# ICs.net
KiCad netlist of a schematic drawn in Altium Designer
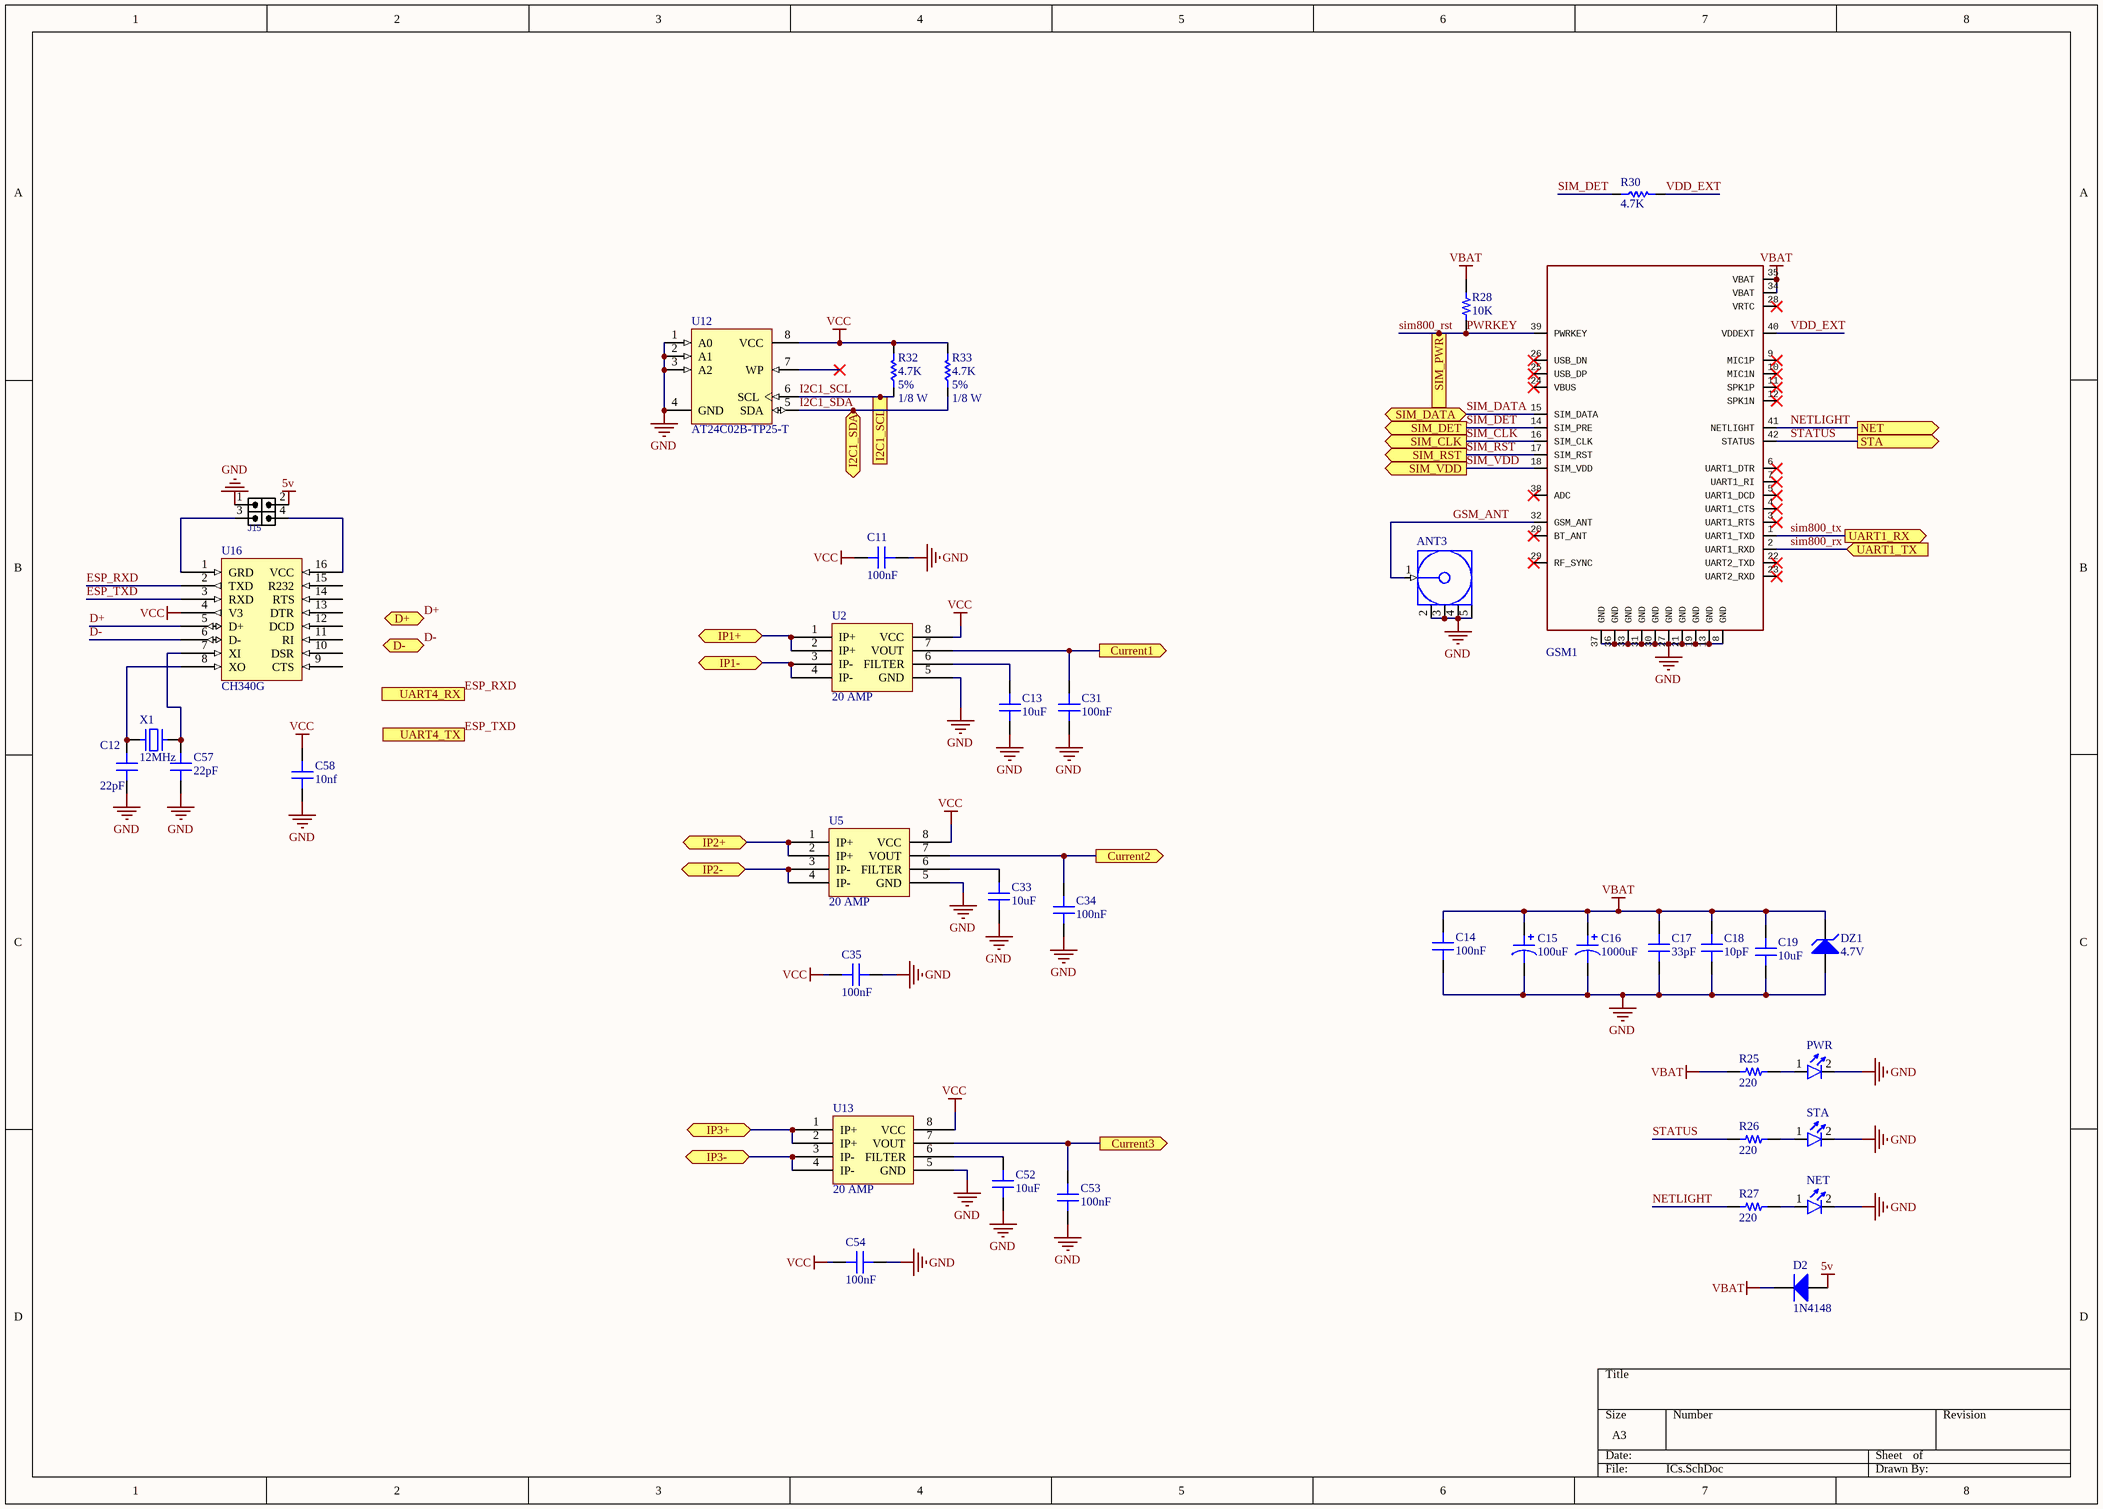
[diagram p0: ICs.SchDoc]

(export (version "E")
  (design (tool "Eeschema 10.0.6"))
  (components
    (comp (ref "ANT3") (value "SMA") (footprint "SMA_RA") (libsource (lib "CONNECTOR") (part "SMA RA")))
    (comp (ref "C11")
      (value "100nF")
      (footprint "CAP 0603_1608")
      (description "SMT Capacitor")
      (libsource (lib "CAPACITOR") (part "Cap SMD 0805"))
    )
    (comp (ref "C12")
      (value "22pF")
      (footprint "CAP 0805")
      (description "SMT Capacitor")
      (libsource (lib "CAPACITOR") (part "Cap SMD 0805"))
    )
    (comp (ref "C13")
      (value "10uF")
      (footprint "CAP 0805")
      (description "SMT Capacitor")
      (libsource (lib "CAPACITOR") (part "Cap SMD 0805"))
    )
    (comp (ref "C14")
      (value "100nF")
      (footprint "CAP 0805")
      (description "SMT Capacitor")
      (libsource (lib "CAPACITOR") (part "Cap SMD 0805"))
    )
    (comp (ref "C15")
      (value "100uF")
      (footprint "CAP TAN SMD 3528")
      (description "SMT TAN Polarised Capacitor")
      (libsource (lib "CAPACITOR") (part "Pol Cap SMD TAN 3528 SIZE B"))
    )
    (comp (ref "C16")
      (value "1000uF")
      (footprint "CAP ALSMD POLY 8.3MM H8.0MM")
      (description "SMT Polarised Capacitor")
      (libsource (lib "CAPACITOR") (part "Pol Cap SMD AL D4 H4"))
    )
    (comp (ref "C17")
      (value "33pF")
      (footprint "CAP 0805")
      (description "SMT Capacitor")
      (libsource (lib "CAPACITOR") (part "Cap SMD 0805"))
    )
    (comp (ref "C18")
      (value "10pF")
      (footprint "CAP 0805")
      (description "SMT Capacitor")
      (libsource (lib "CAPACITOR") (part "Cap SMD 0805"))
    )
    (comp (ref "C19")
      (value "10uF")
      (footprint "CAP 0805")
      (description "SMT Capacitor")
      (libsource (lib "CAPACITOR") (part "Cap SMD 0805"))
    )
    (comp (ref "C31")
      (value "100nF")
      (footprint "CAP 0603_1608")
      (description "SMT Capacitor")
      (libsource (lib "CAPACITOR") (part "Cap SMD 0805"))
    )
    (comp (ref "C33")
      (value "10uF")
      (footprint "CAP 0805")
      (description "SMT Capacitor")
      (libsource (lib "CAPACITOR") (part "Cap SMD 0805"))
    )
    (comp (ref "C34")
      (value "100nF")
      (footprint "CAP 0603_1608")
      (description "SMT Capacitor")
      (libsource (lib "CAPACITOR") (part "Cap SMD 0805"))
    )
    (comp (ref "C35")
      (value "100nF")
      (footprint "CAP 0603_1608")
      (description "SMT Capacitor")
      (libsource (lib "CAPACITOR") (part "Cap SMD 0805"))
    )
    (comp (ref "C52")
      (value "10uF")
      (footprint "CAP 0805_2012")
      (description "SMT Capacitor")
      (libsource (lib "CAPACITOR") (part "Cap SMD 0805"))
    )
    (comp (ref "C53")
      (value "100nF")
      (footprint "CAP 0603_1608")
      (description "SMT Capacitor")
      (libsource (lib "CAPACITOR") (part "Cap SMD 0805"))
    )
    (comp (ref "C54")
      (value "100nF")
      (footprint "CAP 0603_1608")
      (description "SMT Capacitor")
      (libsource (lib "CAPACITOR") (part "Cap SMD 0805"))
    )
    (comp (ref "C57")
      (value "22pF")
      (footprint "CAP 0805")
      (description "SMT Capacitor")
      (libsource (lib "CAPACITOR") (part "Cap SMD 0805"))
    )
    (comp (ref "C58")
      (value "10nf")
      (footprint "CAP 0805")
      (description "SMT Capacitor")
      (libsource (lib "CAPACITOR") (part "Cap SMD 0805"))
    )
    (comp (ref "D2")
      (value "1N4148 SMD")
      (footprint "DO-214AA SMB")
      (description "Signal Diode")
      (fields (field (name "PARAMETER 1") "1N4148"))
      (libsource (lib "DIODE") (part "1N4148 SMD"))
    )
    (comp (ref "DZ1")
      (value "4.7V")
      (footprint "SOD80")
      (description "0.5W Zener")
      (fields (field (name "Comment") "Zener 0.5W SMD"))
      (libsource (lib "DIODE") (part "Zener 0.5W SMD"))
    )
    (comp (ref "GSM1") (value "~") (footprint "SIM800C_M") (libsource (lib "SeyedMojtaba") (part "SIM800C")))
    (comp (ref "J15")
      (value "HDRM_2X2")
      (footprint "HDR_M_2X2")
      (description "CONN, HEADER, Male, pitch: 2.54mm, 4POS")
      (fields (field (name "MANF_P#") "MANF_PART#") (field (name "MANF") "MANF"))
      (libsource (lib "Conn Header") (part "HDR_M_2X2"))
    )
    (comp (ref "NET")
      (value "~")
      (footprint "LED_0603_GREEN")
      (description "LED")
      (fields (field (name "DESIGNER") "Saeid Jorablo"))
      (libsource (lib "My Library") (part "LED"))
    )
    (comp (ref "PWR")
      (value "~")
      (footprint "LED_0603_RED")
      (description "LED")
      (fields (field (name "DESIGNER") "Saeid Jorablo"))
      (libsource (lib "My Library") (part "LED"))
    )
    (comp (ref "R25")
      (value "220")
      (footprint "RES 0805")
      (description "SMD Resistor")
      (libsource (lib "RESISTOR") (part "Res SMD 0805"))
    )
    (comp (ref "R26")
      (value "220")
      (footprint "RES 0805")
      (description "SMD Resistor")
      (libsource (lib "RESISTOR") (part "Res SMD 0805"))
    )
    (comp (ref "R27")
      (value "220")
      (footprint "RES 0805")
      (description "SMD Resistor")
      (libsource (lib "RESISTOR") (part "Res SMD 0805"))
    )
    (comp (ref "R28")
      (value "10K")
      (footprint "RES 0805")
      (description "SMD Resistor")
      (libsource (lib "RESISTOR") (part "Res SMD 0805"))
    )
    (comp (ref "R30")
      (value "4.7K")
      (footprint "RES 0603_1608")
      (description "Resistor")
      (libsource (lib "My Library") (part "Resistor"))
    )
    (comp (ref "R32")
      (value "4.7K")
      (footprint "RES 0603_1608")
      (description "Resistor")
      (fields (field (name "TOLERANCE") "5%") (field (name "POWER") "1/8 W"))
      (libsource (lib "My_Library") (part "Resistor"))
    )
    (comp (ref "R33")
      (value "4.7K")
      (footprint "RES 0603_1608")
      (description "Resistor")
      (fields (field (name "TOLERANCE") "5%") (field (name "POWER") "1/8 W"))
      (libsource (lib "My_Library") (part "Resistor"))
    )
    (comp (ref "STA")
      (value "~")
      (footprint "LED_0603_BLUE")
      (description "LED")
      (fields (field (name "DESIGNER") "Saeid Jorablo"))
      (libsource (lib "My Library") (part "LED"))
    )
    (comp (ref "U2")
      (value "20 AMP")
      (footprint "SOIC_8pin")
      (description "Current Sensor")
      (libsource (lib "Personal") (part "ACS712"))
    )
    (comp (ref "U5")
      (value "20 AMP")
      (footprint "SOIC_8pin")
      (description "Current Sensor")
      (libsource (lib "Personal") (part "ACS712"))
    )
    (comp (ref "U12")
      (value "AT24C02B-TP25-T")
      (footprint "SO8_N")
      (libsource (lib "Atmel Serial EEPROM") (part "AT24C02B-TP25-T"))
    )
    (comp (ref "U13")
      (value "20 AMP")
      (footprint "SOIC_8")
      (description "Current Sensor")
      (libsource (lib "Personal") (part "ACS712"))
    )
    (comp (ref "U16") (value "CH340G") (footprint "SOP16") (libsource (lib "SeyedMojtaba") (part "CH340G")))
    (comp (ref "X1")
      (value "~")
      (footprint "XTAL THD HC49")
      (description "SMT Crystal")
      (fields (field (name "PARAMETER 1") "12MHz"))
      (libsource (lib "CRYSTAL") (part "Crystal THD HC49"))
    )
  )
  (nets
    (net (code "1") (name "/Current1") (class "Default")
      (node (ref "C31") (pin "2") (pinfunction "2_2") (pintype "passive"))
      (node (ref "U2") (pin "7") (pinfunction "VOUT_7") (pintype "passive"))
    )
    (net (code "2") (name "/Current2") (class "Default")
      (node (ref "C34") (pin "1") (pinfunction "1_1") (pintype "passive"))
      (node (ref "U5") (pin "7") (pinfunction "VOUT_7") (pintype "passive"))
    )
    (net (code "3") (name "/Current3") (class "Default")
      (node (ref "C53") (pin "1") (pinfunction "1_1") (pintype "passive"))
      (node (ref "U13") (pin "7") (pinfunction "VOUT_7") (pintype "passive"))
    )
    (net (code "4") (name "/D+") (class "Default")
      (node (ref "U16") (pin "5") (pinfunction "D+_5") (pintype "bidirectional"))
    )
    (net (code "5") (name "/D-") (class "Default")
      (node (ref "U16") (pin "6") (pinfunction "D-_6") (pintype "bidirectional"))
    )
    (net (code "6") (name "/ESP_RXD") (class "Default")
      (node (ref "U16") (pin "2") (pinfunction "TXD_2") (pintype "output"))
    )
    (net (code "7") (name "/ESP_TXD") (class "Default")
      (node (ref "U16") (pin "3") (pinfunction "RXD_3") (pintype "input"))
    )
    (net (code "8") (name "/GSM_ANT") (class "Default")
      (node (ref "ANT3") (pin "1") (pinfunction "Signal_1") (pintype "input"))
      (node (ref "GSM1") (pin "32") (pinfunction "GSM_ANT_32") (pintype "passive"))
    )
    (net (code "9") (name "/I2C1_SCL") (class "Default")
      (node (ref "R32") (pin "1") (pinfunction "1_1") (pintype "passive"))
      (node (ref "U12") (pin "6") (pinfunction "SCL_6") (pintype "input"))
    )
    (net (code "10") (name "/I2C1_SDA") (class "Default")
      (node (ref "R33") (pin "1") (pinfunction "1_1") (pintype "passive"))
      (node (ref "U12") (pin "5") (pinfunction "SDA_5") (pintype "bidirectional"))
    )
    (net (code "11") (name "/IP1+") (class "Default")
      (node (ref "U2") (pin "1") (pinfunction "IP+_1") (pintype "passive"))
      (node (ref "U2") (pin "2") (pinfunction "IP+_2") (pintype "passive"))
    )
    (net (code "12") (name "/IP1-") (class "Default")
      (node (ref "U2") (pin "3") (pinfunction "IP-_3") (pintype "passive"))
      (node (ref "U2") (pin "4") (pinfunction "IP-_4") (pintype "passive"))
    )
    (net (code "13") (name "/IP2+") (class "Default")
      (node (ref "U5") (pin "1") (pinfunction "IP+_1") (pintype "passive"))
      (node (ref "U5") (pin "2") (pinfunction "IP+_2") (pintype "passive"))
    )
    (net (code "14") (name "/IP2-") (class "Default")
      (node (ref "U5") (pin "3") (pinfunction "IP-_3") (pintype "passive"))
      (node (ref "U5") (pin "4") (pinfunction "IP-_4") (pintype "passive"))
    )
    (net (code "15") (name "/IP3+") (class "Default")
      (node (ref "U13") (pin "1") (pinfunction "IP+_1") (pintype "passive"))
      (node (ref "U13") (pin "2") (pinfunction "IP+_2") (pintype "passive"))
    )
    (net (code "16") (name "/IP3-") (class "Default")
      (node (ref "U13") (pin "3") (pinfunction "IP-_3") (pintype "passive"))
      (node (ref "U13") (pin "4") (pinfunction "IP-_4") (pintype "passive"))
    )
    (net (code "17") (name "/NETLIGHT") (class "Default")
      (node (ref "GSM1") (pin "41") (pinfunction "NETLIGHT_41") (pintype "passive"))
      (node (ref "R27") (pin "2") (pinfunction "2_2") (pintype "passive"))
    )
    (net (code "18") (name "/PWRKEY") (class "Default")
      (node (ref "GSM1") (pin "39") (pinfunction "PWRKEY_39") (pintype "passive"))
      (node (ref "R28") (pin "1") (pinfunction "1_1") (pintype "passive"))
    )
    (net (code "19") (name "/SIM_CLK") (class "Default")
      (node (ref "GSM1") (pin "16") (pinfunction "SIM_CLK_16") (pintype "passive"))
    )
    (net (code "20") (name "/SIM_DATA") (class "Default")
      (node (ref "GSM1") (pin "15") (pinfunction "SIM_DATA_15") (pintype "passive"))
    )
    (net (code "21") (name "/SIM_DET") (class "Default")
      (node (ref "GSM1") (pin "14") (pinfunction "SIM_PRE_14") (pintype "passive"))
      (node (ref "R30") (pin "1") (pinfunction "1_1") (pintype "passive"))
    )
    (net (code "22") (name "/SIM_RST") (class "Default")
      (node (ref "GSM1") (pin "17") (pinfunction "SIM_RST_17") (pintype "passive"))
    )
    (net (code "23") (name "/SIM_VDD") (class "Default")
      (node (ref "GSM1") (pin "18") (pinfunction "SIM_VDD_18") (pintype "passive"))
    )
    (net (code "24") (name "/STATUS") (class "Default")
      (node (ref "GSM1") (pin "42") (pinfunction "STATUS_42") (pintype "passive"))
      (node (ref "R26") (pin "2") (pinfunction "2_2") (pintype "passive"))
    )
    (net (code "25") (name "/VDD_EXT") (class "Default")
      (node (ref "GSM1") (pin "40") (pinfunction "VDDEXT_40") (pintype "passive"))
      (node (ref "R30") (pin "2") (pinfunction "2_2") (pintype "passive"))
    )
    (net (code "26") (name "/sim800_rx") (class "Default")
      (node (ref "GSM1") (pin "2") (pinfunction "UART1_RXD_2") (pintype "passive"))
    )
    (net (code "27") (name "/sim800_tx") (class "Default")
      (node (ref "GSM1") (pin "1") (pinfunction "UART1_TXD_1") (pintype "passive"))
    )
    (net (code "28") (name "5v") (class "Default")
      (node (ref "D2") (pin "1") (pinfunction "A_1") (pintype "passive"))
      (node (ref "J15") (pin "2") (pinfunction "2_2") (pintype "passive"))
    )
    (net (code "29") (name "GND") (class "Default")
      (node (ref "ANT3") (pin "2") (pinfunction "GND_2") (pintype "power_in"))
      (node (ref "ANT3") (pin "3") (pinfunction "GND_3") (pintype "power_in"))
      (node (ref "ANT3") (pin "4") (pinfunction "GND_4") (pintype "power_in"))
      (node (ref "ANT3") (pin "5") (pinfunction "GND_5") (pintype "power_in"))
      (node (ref "C11") (pin "1") (pinfunction "1_1") (pintype "passive"))
      (node (ref "C12") (pin "1") (pinfunction "1_1") (pintype "passive"))
      (node (ref "C13") (pin "1") (pinfunction "1_1") (pintype "passive"))
      (node (ref "C14") (pin "1") (pinfunction "1_1") (pintype "passive"))
      (node (ref "C15") (pin "2") (pinfunction "2_2") (pintype "passive"))
      (node (ref "C16") (pin "2") (pinfunction "2_2") (pintype "passive"))
      (node (ref "C17") (pin "1") (pinfunction "1_1") (pintype "passive"))
      (node (ref "C18") (pin "1") (pinfunction "1_1") (pintype "passive"))
      (node (ref "C19") (pin "1") (pinfunction "1_1") (pintype "passive"))
      (node (ref "C31") (pin "1") (pinfunction "1_1") (pintype "passive"))
      (node (ref "C33") (pin "1") (pinfunction "1_1") (pintype "passive"))
      (node (ref "C34") (pin "2") (pinfunction "2_2") (pintype "passive"))
      (node (ref "C35") (pin "1") (pinfunction "1_1") (pintype "passive"))
      (node (ref "C52") (pin "1") (pinfunction "1_1") (pintype "passive"))
      (node (ref "C53") (pin "2") (pinfunction "2_2") (pintype "passive"))
      (node (ref "C54") (pin "1") (pinfunction "1_1") (pintype "passive"))
      (node (ref "C57") (pin "1") (pinfunction "1_1") (pintype "passive"))
      (node (ref "C58") (pin "1") (pinfunction "1_1") (pintype "passive"))
      (node (ref "DZ1") (pin "1") (pinfunction "A_1") (pintype "passive"))
      (node (ref "GSM1") (pin "13") (pinfunction "GND_13") (pintype "passive"))
      (node (ref "GSM1") (pin "19") (pinfunction "GND_19") (pintype "passive"))
      (node (ref "GSM1") (pin "21") (pinfunction "GND_21") (pintype "passive"))
      (node (ref "GSM1") (pin "27") (pinfunction "GND_27") (pintype "passive"))
      (node (ref "GSM1") (pin "30") (pinfunction "GND_30") (pintype "passive"))
      (node (ref "GSM1") (pin "31") (pinfunction "GND_31") (pintype "passive"))
      (node (ref "GSM1") (pin "33") (pinfunction "GND_33") (pintype "passive"))
      (node (ref "GSM1") (pin "36") (pinfunction "GND_36") (pintype "passive"))
      (node (ref "GSM1") (pin "37") (pinfunction "GND_37") (pintype "passive"))
      (node (ref "GSM1") (pin "8") (pinfunction "GND_8") (pintype "passive"))
      (node (ref "J15") (pin "1") (pinfunction "1_1") (pintype "passive"))
      (node (ref "NET") (pin "2") (pinfunction "K_2") (pintype "passive"))
      (node (ref "PWR") (pin "2") (pinfunction "K_2") (pintype "passive"))
      (node (ref "STA") (pin "2") (pinfunction "K_2") (pintype "passive"))
      (node (ref "U12") (pin "1") (pinfunction "A0_1") (pintype "input"))
      (node (ref "U12") (pin "2") (pinfunction "A1_2") (pintype "input"))
      (node (ref "U12") (pin "3") (pinfunction "A2_3") (pintype "input"))
      (node (ref "U12") (pin "4") (pinfunction "GND_4") (pintype "power_in"))
      (node (ref "U13") (pin "5") (pinfunction "GND_5") (pintype "passive"))
      (node (ref "U2") (pin "5") (pinfunction "GND_5") (pintype "passive"))
      (node (ref "U5") (pin "5") (pinfunction "GND_5") (pintype "passive"))
    )
    (net (code "30") (name "Net-(NET-A)") (class "Default")
      (node (ref "NET") (pin "1") (pinfunction "A_1") (pintype "passive"))
      (node (ref "R27") (pin "1") (pinfunction "1_1") (pintype "passive"))
    )
    (net (code "31") (name "Net-(PWR-A)") (class "Default")
      (node (ref "PWR") (pin "1") (pinfunction "A_1") (pintype "passive"))
      (node (ref "R25") (pin "1") (pinfunction "1_1") (pintype "passive"))
    )
    (net (code "32") (name "Net-(STA-A)") (class "Default")
      (node (ref "R26") (pin "1") (pinfunction "1_1") (pintype "passive"))
      (node (ref "STA") (pin "1") (pinfunction "A_1") (pintype "passive"))
    )
    (net (code "33") (name "Net-(U2-FILTER)") (class "Default")
      (node (ref "C13") (pin "2") (pinfunction "2_2") (pintype "passive"))
      (node (ref "U2") (pin "6") (pinfunction "FILTER_6") (pintype "passive"))
    )
    (net (code "34") (name "Net-(U5-FILTER)") (class "Default")
      (node (ref "C33") (pin "2") (pinfunction "2_2") (pintype "passive"))
      (node (ref "U5") (pin "6") (pinfunction "FILTER_6") (pintype "passive"))
    )
    (net (code "35") (name "Net-(U13-FILTER)") (class "Default")
      (node (ref "C52") (pin "2") (pinfunction "2_2") (pintype "passive"))
      (node (ref "U13") (pin "6") (pinfunction "FILTER_6") (pintype "passive"))
    )
    (net (code "36") (name "Net-(U16-GRD)") (class "Default")
      (node (ref "J15") (pin "3") (pinfunction "3_3") (pintype "passive"))
      (node (ref "U16") (pin "1") (pinfunction "GRD_1") (pintype "input"))
    )
    (net (code "37") (name "Net-(U16-VCC)") (class "Default")
      (node (ref "J15") (pin "4") (pinfunction "4_4") (pintype "passive"))
      (node (ref "U16") (pin "16") (pinfunction "VCC_16") (pintype "input"))
    )
    (net (code "38") (name "Net-(U16-XI)") (class "Default")
      (node (ref "C57") (pin "2") (pinfunction "2_2") (pintype "passive"))
      (node (ref "U16") (pin "7") (pinfunction "XI_7") (pintype "input"))
      (node (ref "X1") (pin "2") (pinfunction "2_2") (pintype "passive"))
    )
    (net (code "39") (name "Net-(U16-XO)") (class "Default")
      (node (ref "C12") (pin "2") (pinfunction "2_2") (pintype "passive"))
      (node (ref "U16") (pin "8") (pinfunction "XO_8") (pintype "input"))
      (node (ref "X1") (pin "1") (pinfunction "1_1") (pintype "passive"))
    )
    (net (code "40") (name "VBAT") (class "Default")
      (node (ref "C14") (pin "2") (pinfunction "2_2") (pintype "passive"))
      (node (ref "C15") (pin "1") (pinfunction "1_1") (pintype "passive"))
      (node (ref "C16") (pin "1") (pinfunction "1_1") (pintype "passive"))
      (node (ref "C17") (pin "2") (pinfunction "2_2") (pintype "passive"))
      (node (ref "C18") (pin "2") (pinfunction "2_2") (pintype "passive"))
      (node (ref "C19") (pin "2") (pinfunction "2_2") (pintype "passive"))
      (node (ref "D2") (pin "2") (pinfunction "K_2") (pintype "passive"))
      (node (ref "DZ1") (pin "2") (pinfunction "K_2") (pintype "passive"))
      (node (ref "GSM1") (pin "34") (pinfunction "VBAT_34") (pintype "passive"))
      (node (ref "GSM1") (pin "35") (pinfunction "VBAT_35") (pintype "passive"))
      (node (ref "R25") (pin "2") (pinfunction "2_2") (pintype "passive"))
      (node (ref "R28") (pin "2") (pinfunction "2_2") (pintype "passive"))
    )
    (net (code "41") (name "VCC") (class "Default")
      (node (ref "C11") (pin "2") (pinfunction "2_2") (pintype "passive"))
      (node (ref "C35") (pin "2") (pinfunction "2_2") (pintype "passive"))
      (node (ref "C54") (pin "2") (pinfunction "2_2") (pintype "passive"))
      (node (ref "C58") (pin "2") (pinfunction "2_2") (pintype "passive"))
      (node (ref "R32") (pin "2") (pinfunction "2_2") (pintype "passive"))
      (node (ref "R33") (pin "2") (pinfunction "2_2") (pintype "passive"))
      (node (ref "U12") (pin "8") (pinfunction "VCC_8") (pintype "power_in"))
      (node (ref "U13") (pin "8") (pinfunction "VCC_8") (pintype "passive"))
      (node (ref "U16") (pin "4") (pinfunction "V3_4") (pintype "output"))
      (node (ref "U2") (pin "8") (pinfunction "VCC_8") (pintype "passive"))
      (node (ref "U5") (pin "8") (pinfunction "VCC_8") (pintype "passive"))
    )
    (net (code "42") (name "unconnected-(GSM1-ADC-Pad38)") (class "Default")
      (node (ref "GSM1") (pin "38") (pinfunction "ADC_38") (pintype "passive+no_connect"))
    )
    (net (code "43") (name "unconnected-(GSM1-BT_ANT-Pad20)") (class "Default")
      (node (ref "GSM1") (pin "20") (pinfunction "BT_ANT_20") (pintype "passive+no_connect"))
    )
    (net (code "44") (name "unconnected-(GSM1-MIC1N-Pad10)") (class "Default")
      (node (ref "GSM1") (pin "10") (pinfunction "MIC1N_10") (pintype "passive+no_connect"))
    )
    (net (code "45") (name "unconnected-(GSM1-MIC1P-Pad9)") (class "Default")
      (node (ref "GSM1") (pin "9") (pinfunction "MIC1P_9") (pintype "passive+no_connect"))
    )
    (net (code "46") (name "unconnected-(GSM1-RF_SYNC-Pad29)") (class "Default")
      (node (ref "GSM1") (pin "29") (pinfunction "RF_SYNC_29") (pintype "passive+no_connect"))
    )
    (net (code "47") (name "unconnected-(GSM1-SPK1N-Pad12)") (class "Default")
      (node (ref "GSM1") (pin "12") (pinfunction "SPK1N_12") (pintype "passive+no_connect"))
    )
    (net (code "48") (name "unconnected-(GSM1-SPK1P-Pad11)") (class "Default")
      (node (ref "GSM1") (pin "11") (pinfunction "SPK1P_11") (pintype "passive+no_connect"))
    )
    (net (code "49") (name "unconnected-(GSM1-UART1_CTS-Pad4)") (class "Default")
      (node (ref "GSM1") (pin "4") (pinfunction "UART1_CTS_4") (pintype "passive+no_connect"))
    )
    (net (code "50") (name "unconnected-(GSM1-UART1_DCD-Pad5)") (class "Default")
      (node (ref "GSM1") (pin "5") (pinfunction "UART1_DCD_5") (pintype "passive+no_connect"))
    )
    (net (code "51") (name "unconnected-(GSM1-UART1_DTR-Pad6)") (class "Default")
      (node (ref "GSM1") (pin "6") (pinfunction "UART1_DTR_6") (pintype "passive+no_connect"))
    )
    (net (code "52") (name "unconnected-(GSM1-UART1_RI-Pad7)") (class "Default")
      (node (ref "GSM1") (pin "7") (pinfunction "UART1_RI_7") (pintype "passive+no_connect"))
    )
    (net (code "53") (name "unconnected-(GSM1-UART1_RTS-Pad3)") (class "Default")
      (node (ref "GSM1") (pin "3") (pinfunction "UART1_RTS_3") (pintype "passive+no_connect"))
    )
    (net (code "54") (name "unconnected-(GSM1-UART2_RXD-Pad23)") (class "Default")
      (node (ref "GSM1") (pin "23") (pinfunction "UART2_RXD_23") (pintype "passive+no_connect"))
    )
    (net (code "55") (name "unconnected-(GSM1-UART2_TXD-Pad22)") (class "Default")
      (node (ref "GSM1") (pin "22") (pinfunction "UART2_TXD_22") (pintype "passive+no_connect"))
    )
    (net (code "56") (name "unconnected-(GSM1-USB_DN-Pad26)") (class "Default")
      (node (ref "GSM1") (pin "26") (pinfunction "USB_DN_26") (pintype "passive+no_connect"))
    )
    (net (code "57") (name "unconnected-(GSM1-USB_DP-Pad25)") (class "Default")
      (node (ref "GSM1") (pin "25") (pinfunction "USB_DP_25") (pintype "passive+no_connect"))
    )
    (net (code "58") (name "unconnected-(GSM1-VBUS-Pad24)") (class "Default")
      (node (ref "GSM1") (pin "24") (pinfunction "VBUS_24") (pintype "passive+no_connect"))
    )
    (net (code "59") (name "unconnected-(GSM1-VRTC-Pad28)") (class "Default")
      (node (ref "GSM1") (pin "28") (pinfunction "VRTC_28") (pintype "passive+no_connect"))
    )
    (net (code "60") (name "unconnected-(U12-WP-Pad7)") (class "Default")
      (node (ref "U12") (pin "7") (pinfunction "WP_7") (pintype "input+no_connect"))
    )
    (net (code "61") (name "unconnected-(U16-CTS-Pad9)") (class "Default")
      (node (ref "U16") (pin "9") (pinfunction "CTS_9") (pintype "input"))
    )
    (net (code "62") (name "unconnected-(U16-DCD-Pad12)") (class "Default")
      (node (ref "U16") (pin "12") (pinfunction "DCD_12") (pintype "input"))
    )
    (net (code "63") (name "unconnected-(U16-DSR-Pad10)") (class "Default")
      (node (ref "U16") (pin "10") (pinfunction "DSR_10") (pintype "input"))
    )
    (net (code "64") (name "unconnected-(U16-DTR-Pad13)") (class "Default")
      (node (ref "U16") (pin "13") (pinfunction "DTR_13") (pintype "input"))
    )
    (net (code "65") (name "unconnected-(U16-R232-Pad15)") (class "Default")
      (node (ref "U16") (pin "15") (pinfunction "R232_15") (pintype "input"))
    )
    (net (code "66") (name "unconnected-(U16-RI-Pad11)") (class "Default")
      (node (ref "U16") (pin "11") (pinfunction "RI_11") (pintype "input"))
    )
    (net (code "67") (name "unconnected-(U16-RTS-Pad14)") (class "Default")
      (node (ref "U16") (pin "14") (pinfunction "RTS_14") (pintype "input"))
    )
  )
)
